# Input_block.net
KiCad netlist of a schematic drawn in Altium Designer
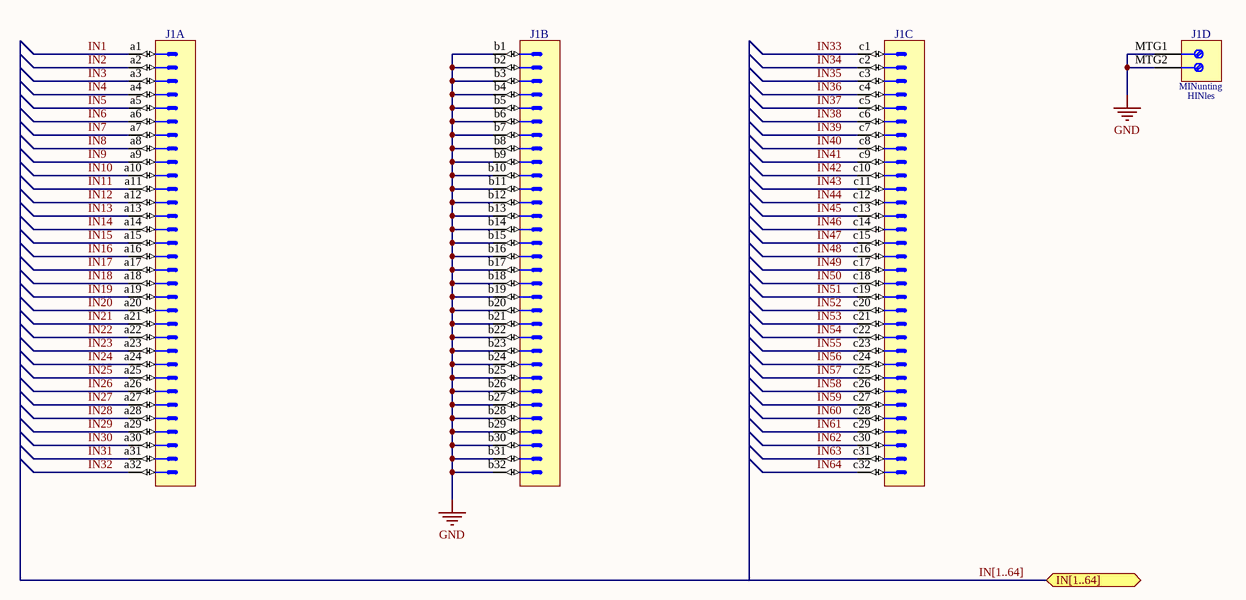
[diagram p0: Input_block.SchDoc]

(export (version "E")
  (design (tool "Eeschema 10.0.6"))
  (components
    (comp (ref "J1")
      (value "DIN 41612 Type C")
      (footprint "HARTING_09 03 196 6921")
      (description "Connector 96abc male (3x32)")
      (fields
        (field (name "PART NUMBER") "HARTING_09 03 196 6921")
        (field (name "MANUFACTURER") "HARTING")
        (field (name "AUTHOR") "CERN DEM JMW")
      )
      (libsource (lib "Connectors") (part "Connector 96abc male (3x32)"))
    )
  )
  (nets
    (net (code "1") (name "/IN1") (class "Default")
      (node (ref "J1") (pin "a1") (pinfunction "a1_a1") (pintype "bidirectional"))
    )
    (net (code "2") (name "/IN2") (class "Default")
      (node (ref "J1") (pin "a2") (pinfunction "a2_a2") (pintype "bidirectional"))
    )
    (net (code "3") (name "/IN3") (class "Default")
      (node (ref "J1") (pin "a3") (pinfunction "a3_a3") (pintype "bidirectional"))
    )
    (net (code "4") (name "/IN4") (class "Default")
      (node (ref "J1") (pin "a4") (pinfunction "a4_a4") (pintype "bidirectional"))
    )
    (net (code "5") (name "/IN5") (class "Default")
      (node (ref "J1") (pin "a5") (pinfunction "a5_a5") (pintype "bidirectional"))
    )
    (net (code "6") (name "/IN6") (class "Default")
      (node (ref "J1") (pin "a6") (pinfunction "a6_a6") (pintype "bidirectional"))
    )
    (net (code "7") (name "/IN7") (class "Default")
      (node (ref "J1") (pin "a7") (pinfunction "a7_a7") (pintype "bidirectional"))
    )
    (net (code "8") (name "/IN8") (class "Default")
      (node (ref "J1") (pin "a8") (pinfunction "a8_a8") (pintype "bidirectional"))
    )
    (net (code "9") (name "/IN9") (class "Default")
      (node (ref "J1") (pin "a9") (pinfunction "a9_a9") (pintype "bidirectional"))
    )
    (net (code "10") (name "/IN10") (class "Default")
      (node (ref "J1") (pin "a10") (pinfunction "a10_a10") (pintype "bidirectional"))
    )
    (net (code "11") (name "/IN11") (class "Default")
      (node (ref "J1") (pin "a11") (pinfunction "a11_a11") (pintype "bidirectional"))
    )
    (net (code "12") (name "/IN12") (class "Default")
      (node (ref "J1") (pin "a12") (pinfunction "a12_a12") (pintype "bidirectional"))
    )
    (net (code "13") (name "/IN13") (class "Default")
      (node (ref "J1") (pin "a13") (pinfunction "a13_a13") (pintype "bidirectional"))
    )
    (net (code "14") (name "/IN14") (class "Default")
      (node (ref "J1") (pin "a14") (pinfunction "a14_a14") (pintype "bidirectional"))
    )
    (net (code "15") (name "/IN15") (class "Default")
      (node (ref "J1") (pin "a15") (pinfunction "a15_a15") (pintype "bidirectional"))
    )
    (net (code "16") (name "/IN16") (class "Default")
      (node (ref "J1") (pin "a16") (pinfunction "a16_a16") (pintype "bidirectional"))
    )
    (net (code "17") (name "/IN17") (class "Default")
      (node (ref "J1") (pin "a17") (pinfunction "a17_a17") (pintype "bidirectional"))
    )
    (net (code "18") (name "/IN18") (class "Default")
      (node (ref "J1") (pin "a18") (pinfunction "a18_a18") (pintype "bidirectional"))
    )
    (net (code "19") (name "/IN19") (class "Default")
      (node (ref "J1") (pin "a19") (pinfunction "a19_a19") (pintype "bidirectional"))
    )
    (net (code "20") (name "/IN20") (class "Default")
      (node (ref "J1") (pin "a20") (pinfunction "a20_a20") (pintype "bidirectional"))
    )
    (net (code "21") (name "/IN21") (class "Default")
      (node (ref "J1") (pin "a21") (pinfunction "a21_a21") (pintype "bidirectional"))
    )
    (net (code "22") (name "/IN22") (class "Default")
      (node (ref "J1") (pin "a22") (pinfunction "a22_a22") (pintype "bidirectional"))
    )
    (net (code "23") (name "/IN23") (class "Default")
      (node (ref "J1") (pin "a23") (pinfunction "a23_a23") (pintype "bidirectional"))
    )
    (net (code "24") (name "/IN24") (class "Default")
      (node (ref "J1") (pin "a24") (pinfunction "a24_a24") (pintype "bidirectional"))
    )
    (net (code "25") (name "/IN25") (class "Default")
      (node (ref "J1") (pin "a25") (pinfunction "a25_a25") (pintype "bidirectional"))
    )
    (net (code "26") (name "/IN26") (class "Default")
      (node (ref "J1") (pin "a26") (pinfunction "a26_a26") (pintype "bidirectional"))
    )
    (net (code "27") (name "/IN27") (class "Default")
      (node (ref "J1") (pin "a27") (pinfunction "a27_a27") (pintype "bidirectional"))
    )
    (net (code "28") (name "/IN28") (class "Default")
      (node (ref "J1") (pin "a28") (pinfunction "a28_a28") (pintype "bidirectional"))
    )
    (net (code "29") (name "/IN29") (class "Default")
      (node (ref "J1") (pin "a29") (pinfunction "a29_a29") (pintype "bidirectional"))
    )
    (net (code "30") (name "/IN30") (class "Default")
      (node (ref "J1") (pin "a30") (pinfunction "a30_a30") (pintype "bidirectional"))
    )
    (net (code "31") (name "/IN31") (class "Default")
      (node (ref "J1") (pin "a31") (pinfunction "a31_a31") (pintype "bidirectional"))
    )
    (net (code "32") (name "/IN32") (class "Default")
      (node (ref "J1") (pin "a32") (pinfunction "a32_a32") (pintype "bidirectional"))
    )
    (net (code "33") (name "/IN33") (class "Default")
      (node (ref "J1") (pin "c1") (pinfunction "c1_c1") (pintype "bidirectional"))
    )
    (net (code "34") (name "/IN34") (class "Default")
      (node (ref "J1") (pin "c2") (pinfunction "c2_c2") (pintype "bidirectional"))
    )
    (net (code "35") (name "/IN35") (class "Default")
      (node (ref "J1") (pin "c3") (pinfunction "c3_c3") (pintype "bidirectional"))
    )
    (net (code "36") (name "/IN36") (class "Default")
      (node (ref "J1") (pin "c4") (pinfunction "c4_c4") (pintype "bidirectional"))
    )
    (net (code "37") (name "/IN37") (class "Default")
      (node (ref "J1") (pin "c5") (pinfunction "c5_c5") (pintype "bidirectional"))
    )
    (net (code "38") (name "/IN38") (class "Default")
      (node (ref "J1") (pin "c6") (pinfunction "c6_c6") (pintype "bidirectional"))
    )
    (net (code "39") (name "/IN39") (class "Default")
      (node (ref "J1") (pin "c7") (pinfunction "c7_c7") (pintype "bidirectional"))
    )
    (net (code "40") (name "/IN40") (class "Default")
      (node (ref "J1") (pin "c8") (pinfunction "c8_c8") (pintype "bidirectional"))
    )
    (net (code "41") (name "/IN41") (class "Default")
      (node (ref "J1") (pin "c9") (pinfunction "c9_c9") (pintype "bidirectional"))
    )
    (net (code "42") (name "/IN42") (class "Default")
      (node (ref "J1") (pin "c10") (pinfunction "c10_c10") (pintype "bidirectional"))
    )
    (net (code "43") (name "/IN43") (class "Default")
      (node (ref "J1") (pin "c11") (pinfunction "c11_c11") (pintype "bidirectional"))
    )
    (net (code "44") (name "/IN44") (class "Default")
      (node (ref "J1") (pin "c12") (pinfunction "c12_c12") (pintype "bidirectional"))
    )
    (net (code "45") (name "/IN45") (class "Default")
      (node (ref "J1") (pin "c13") (pinfunction "c13_c13") (pintype "bidirectional"))
    )
    (net (code "46") (name "/IN46") (class "Default")
      (node (ref "J1") (pin "c14") (pinfunction "c14_c14") (pintype "bidirectional"))
    )
    (net (code "47") (name "/IN47") (class "Default")
      (node (ref "J1") (pin "c15") (pinfunction "c15_c15") (pintype "bidirectional"))
    )
    (net (code "48") (name "/IN48") (class "Default")
      (node (ref "J1") (pin "c16") (pinfunction "c16_c16") (pintype "bidirectional"))
    )
    (net (code "49") (name "/IN49") (class "Default")
      (node (ref "J1") (pin "c17") (pinfunction "c17_c17") (pintype "bidirectional"))
    )
    (net (code "50") (name "/IN50") (class "Default")
      (node (ref "J1") (pin "c18") (pinfunction "c18_c18") (pintype "bidirectional"))
    )
    (net (code "51") (name "/IN51") (class "Default")
      (node (ref "J1") (pin "c19") (pinfunction "c19_c19") (pintype "bidirectional"))
    )
    (net (code "52") (name "/IN52") (class "Default")
      (node (ref "J1") (pin "c20") (pinfunction "c20_c20") (pintype "bidirectional"))
    )
    (net (code "53") (name "/IN53") (class "Default")
      (node (ref "J1") (pin "c21") (pinfunction "c21_c21") (pintype "bidirectional"))
    )
    (net (code "54") (name "/IN54") (class "Default")
      (node (ref "J1") (pin "c22") (pinfunction "c22_c22") (pintype "bidirectional"))
    )
    (net (code "55") (name "/IN55") (class "Default")
      (node (ref "J1") (pin "c23") (pinfunction "c23_c23") (pintype "bidirectional"))
    )
    (net (code "56") (name "/IN56") (class "Default")
      (node (ref "J1") (pin "c24") (pinfunction "c24_c24") (pintype "bidirectional"))
    )
    (net (code "57") (name "/IN57") (class "Default")
      (node (ref "J1") (pin "c25") (pinfunction "c25_c25") (pintype "bidirectional"))
    )
    (net (code "58") (name "/IN58") (class "Default")
      (node (ref "J1") (pin "c26") (pinfunction "c26_c26") (pintype "bidirectional"))
    )
    (net (code "59") (name "/IN59") (class "Default")
      (node (ref "J1") (pin "c27") (pinfunction "c27_c27") (pintype "bidirectional"))
    )
    (net (code "60") (name "/IN60") (class "Default")
      (node (ref "J1") (pin "c28") (pinfunction "c28_c28") (pintype "bidirectional"))
    )
    (net (code "61") (name "/IN61") (class "Default")
      (node (ref "J1") (pin "c29") (pinfunction "c29_c29") (pintype "bidirectional"))
    )
    (net (code "62") (name "/IN62") (class "Default")
      (node (ref "J1") (pin "c30") (pinfunction "c30_c30") (pintype "bidirectional"))
    )
    (net (code "63") (name "/IN63") (class "Default")
      (node (ref "J1") (pin "c31") (pinfunction "c31_c31") (pintype "bidirectional"))
    )
    (net (code "64") (name "/IN64") (class "Default")
      (node (ref "J1") (pin "c32") (pinfunction "c32_c32") (pintype "bidirectional"))
    )
    (net (code "66") (name "GND") (class "Default")
      (node (ref "J1") (pin "MTG1") (pinfunction "MTG1_MTG1") (pintype "passive"))
      (node (ref "J1") (pin "MTG2") (pinfunction "MTG2_MTG2") (pintype "passive"))
      (node (ref "J1") (pin "b1") (pinfunction "b1_b1") (pintype "bidirectional"))
      (node (ref "J1") (pin "b10") (pinfunction "b10_b10") (pintype "bidirectional"))
      (node (ref "J1") (pin "b11") (pinfunction "b11_b11") (pintype "bidirectional"))
      (node (ref "J1") (pin "b12") (pinfunction "b12_b12") (pintype "bidirectional"))
      (node (ref "J1") (pin "b13") (pinfunction "b13_b13") (pintype "bidirectional"))
      (node (ref "J1") (pin "b14") (pinfunction "b14_b14") (pintype "bidirectional"))
      (node (ref "J1") (pin "b15") (pinfunction "b15_b15") (pintype "bidirectional"))
      (node (ref "J1") (pin "b16") (pinfunction "b16_b16") (pintype "bidirectional"))
      (node (ref "J1") (pin "b17") (pinfunction "b17_b17") (pintype "bidirectional"))
      (node (ref "J1") (pin "b18") (pinfunction "b18_b18") (pintype "bidirectional"))
      (node (ref "J1") (pin "b19") (pinfunction "b19_b19") (pintype "bidirectional"))
      (node (ref "J1") (pin "b2") (pinfunction "b2_b2") (pintype "bidirectional"))
      (node (ref "J1") (pin "b20") (pinfunction "b20_b20") (pintype "bidirectional"))
      (node (ref "J1") (pin "b21") (pinfunction "b21_b21") (pintype "bidirectional"))
      (node (ref "J1") (pin "b22") (pinfunction "b22_b22") (pintype "bidirectional"))
      (node (ref "J1") (pin "b23") (pinfunction "b23_b23") (pintype "bidirectional"))
      (node (ref "J1") (pin "b24") (pinfunction "b24_b24") (pintype "bidirectional"))
      (node (ref "J1") (pin "b25") (pinfunction "b25_b25") (pintype "bidirectional"))
      (node (ref "J1") (pin "b26") (pinfunction "b26_b26") (pintype "bidirectional"))
      (node (ref "J1") (pin "b27") (pinfunction "b27_b27") (pintype "bidirectional"))
      (node (ref "J1") (pin "b28") (pinfunction "b28_b28") (pintype "bidirectional"))
      (node (ref "J1") (pin "b29") (pinfunction "b29_b29") (pintype "bidirectional"))
      (node (ref "J1") (pin "b3") (pinfunction "b3_b3") (pintype "bidirectional"))
      (node (ref "J1") (pin "b30") (pinfunction "b30_b30") (pintype "bidirectional"))
      (node (ref "J1") (pin "b31") (pinfunction "b31_b31") (pintype "bidirectional"))
      (node (ref "J1") (pin "b32") (pinfunction "b32_b32") (pintype "bidirectional"))
      (node (ref "J1") (pin "b4") (pinfunction "b4_b4") (pintype "bidirectional"))
      (node (ref "J1") (pin "b5") (pinfunction "b5_b5") (pintype "bidirectional"))
      (node (ref "J1") (pin "b6") (pinfunction "b6_b6") (pintype "bidirectional"))
      (node (ref "J1") (pin "b7") (pinfunction "b7_b7") (pintype "bidirectional"))
      (node (ref "J1") (pin "b8") (pinfunction "b8_b8") (pintype "bidirectional"))
      (node (ref "J1") (pin "b9") (pinfunction "b9_b9") (pintype "bidirectional"))
    )
  )
)
